# KoncovaCast_multi.net
KiCad netlist of a schematic drawn in EAGLE
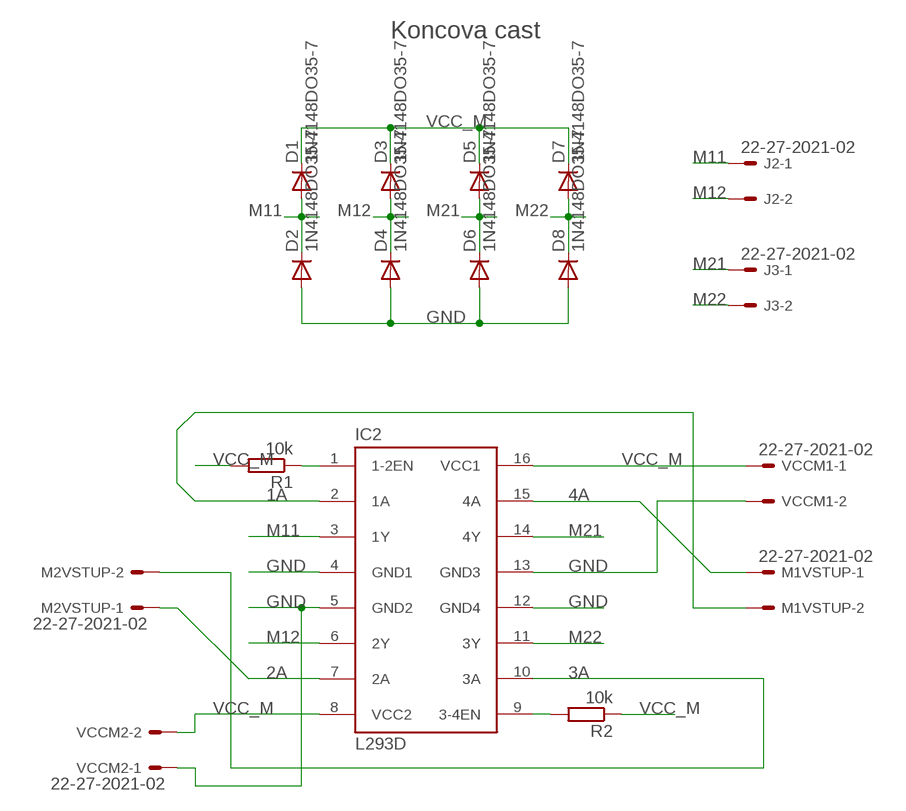
[diagram p0: schematic, sheet 1]

(export (version "E")
  (design (tool "Eeschema 10.0.6"))
  (components
    (comp (ref "D1")
      (value "1N4148DO35-7")
      (footprint "eagle-import:DO35-7")
      (libsource (lib "eagle-import") (part "1N4148DO35-7"))
    )
    (comp (ref "D2")
      (value "1N4148DO35-7")
      (footprint "eagle-import:DO35-7")
      (libsource (lib "eagle-import") (part "1N4148DO35-7"))
    )
    (comp (ref "D3")
      (value "1N4148DO35-7")
      (footprint "eagle-import:DO35-7")
      (libsource (lib "eagle-import") (part "1N4148DO35-7"))
    )
    (comp (ref "D4")
      (value "1N4148DO35-7")
      (footprint "eagle-import:DO35-7")
      (libsource (lib "eagle-import") (part "1N4148DO35-7"))
    )
    (comp (ref "D5")
      (value "1N4148DO35-7")
      (footprint "eagle-import:DO35-7")
      (libsource (lib "eagle-import") (part "1N4148DO35-7"))
    )
    (comp (ref "D6")
      (value "1N4148DO35-7")
      (footprint "eagle-import:DO35-7")
      (libsource (lib "eagle-import") (part "1N4148DO35-7"))
    )
    (comp (ref "D7")
      (value "1N4148DO35-7")
      (footprint "eagle-import:DO35-7")
      (libsource (lib "eagle-import") (part "1N4148DO35-7"))
    )
    (comp (ref "D8")
      (value "1N4148DO35-7")
      (footprint "eagle-import:DO35-7")
      (libsource (lib "eagle-import") (part "1N4148DO35-7"))
    )
    (comp (ref "IC2")
      (value "L293D")
      (footprint "eagle-import:DIL16")
      (libsource (lib "eagle-import") (part "L293D"))
    )
    (comp (ref "J2")
      (value "22-27-2021-02")
      (footprint "eagle-import:6410-02")
      (libsource (lib "eagle-import") (part "22-?-0227-2021"))
    )
    (comp (ref "J3")
      (value "22-27-2021-02")
      (footprint "eagle-import:6410-02")
      (libsource (lib "eagle-import") (part "22-?-0227-2021"))
    )
    (comp (ref "M1VSTUP")
      (value "22-27-2021-02")
      (footprint "eagle-import:6410-02")
      (libsource (lib "eagle-import") (part "22-?-0227-2021"))
    )
    (comp (ref "M2VSTUP")
      (value "22-27-2021-02")
      (footprint "eagle-import:6410-02")
      (libsource (lib "eagle-import") (part "22-?-0227-2021"))
    )
    (comp (ref "R1")
      (value "10k")
      (footprint "eagle-import:0204V")
      (libsource (lib "eagle-import") (part "R-EU_0204/2V"))
    )
    (comp (ref "R2")
      (value "10k")
      (footprint "eagle-import:0204V")
      (libsource (lib "eagle-import") (part "R-EU_0204/2V"))
    )
    (comp (ref "VCCM1")
      (value "22-27-2021-02")
      (footprint "eagle-import:6410-02")
      (libsource (lib "eagle-import") (part "22-?-0227-2021"))
    )
    (comp (ref "VCCM2")
      (value "22-27-2021-02")
      (footprint "eagle-import:6410-02")
      (libsource (lib "eagle-import") (part "22-?-0227-2021"))
    )
  )
  (nets
    (net (code "1") (name "/1A") (class "Default")
      (node (ref "IC2") (pin "2") (pinfunction "1A_2") (pintype "input"))
      (node (ref "M1VSTUP") (pin "2") (pinfunction "S_2") (pintype "passive"))
    )
    (net (code "2") (name "/2A") (class "Default")
      (node (ref "IC2") (pin "7") (pinfunction "2A_7") (pintype "input"))
      (node (ref "M2VSTUP") (pin "1") (pinfunction "S_1") (pintype "passive"))
    )
    (net (code "3") (name "/3A") (class "Default")
      (node (ref "IC2") (pin "10") (pinfunction "3A_10") (pintype "input"))
      (node (ref "M2VSTUP") (pin "2") (pinfunction "S_2") (pintype "passive"))
    )
    (net (code "4") (name "/4A") (class "Default")
      (node (ref "IC2") (pin "15") (pinfunction "4A_15") (pintype "input"))
      (node (ref "M1VSTUP") (pin "1") (pinfunction "S_1") (pintype "passive"))
    )
    (net (code "5") (name "/GND") (class "Default")
      (node (ref "D2") (pin "A") (pinfunction "A_A") (pintype "passive"))
      (node (ref "D4") (pin "A") (pinfunction "A_A") (pintype "passive"))
      (node (ref "D6") (pin "A") (pinfunction "A_A") (pintype "passive"))
      (node (ref "D8") (pin "A") (pinfunction "A_A") (pintype "passive"))
      (node (ref "IC2") (pin "12") (pinfunction "GND4_12") (pintype "power_in"))
      (node (ref "IC2") (pin "13") (pinfunction "GND3_13") (pintype "power_in"))
      (node (ref "IC2") (pin "4") (pinfunction "GND1_4") (pintype "power_in"))
      (node (ref "IC2") (pin "5") (pinfunction "GND2_5") (pintype "power_in"))
      (node (ref "VCCM1") (pin "2") (pinfunction "S_2") (pintype "passive"))
      (node (ref "VCCM2") (pin "1") (pinfunction "S_1") (pintype "passive"))
    )
    (net (code "6") (name "/M11") (class "Default")
      (node (ref "D1") (pin "A") (pinfunction "A_A") (pintype "passive"))
      (node (ref "D2") (pin "C") (pinfunction "C_C") (pintype "passive"))
      (node (ref "IC2") (pin "3") (pinfunction "1Y_3") (pintype "output"))
      (node (ref "J2") (pin "1") (pinfunction "S_1") (pintype "passive"))
    )
    (net (code "7") (name "/M12") (class "Default")
      (node (ref "D3") (pin "A") (pinfunction "A_A") (pintype "passive"))
      (node (ref "D4") (pin "C") (pinfunction "C_C") (pintype "passive"))
      (node (ref "IC2") (pin "6") (pinfunction "2Y_6") (pintype "output"))
      (node (ref "J2") (pin "2") (pinfunction "S_2") (pintype "passive"))
    )
    (net (code "8") (name "/M21") (class "Default")
      (node (ref "D5") (pin "A") (pinfunction "A_A") (pintype "passive"))
      (node (ref "D6") (pin "C") (pinfunction "C_C") (pintype "passive"))
      (node (ref "IC2") (pin "14") (pinfunction "4Y_14") (pintype "output"))
      (node (ref "J3") (pin "1") (pinfunction "S_1") (pintype "passive"))
    )
    (net (code "9") (name "/M22") (class "Default")
      (node (ref "D7") (pin "A") (pinfunction "A_A") (pintype "passive"))
      (node (ref "D8") (pin "C") (pinfunction "C_C") (pintype "passive"))
      (node (ref "IC2") (pin "11") (pinfunction "3Y_11") (pintype "output"))
      (node (ref "J3") (pin "2") (pinfunction "S_2") (pintype "passive"))
    )
    (net (code "10") (name "/VCC_M") (class "Default")
      (node (ref "D1") (pin "C") (pinfunction "C_C") (pintype "passive"))
      (node (ref "D3") (pin "C") (pinfunction "C_C") (pintype "passive"))
      (node (ref "D5") (pin "C") (pinfunction "C_C") (pintype "passive"))
      (node (ref "D7") (pin "C") (pinfunction "C_C") (pintype "passive"))
      (node (ref "IC2") (pin "16") (pinfunction "VCC1_16") (pintype "power_in"))
      (node (ref "IC2") (pin "8") (pinfunction "VCC2_8") (pintype "power_in"))
      (node (ref "R1") (pin "2") (pinfunction "2_2") (pintype "passive"))
      (node (ref "R2") (pin "1") (pinfunction "1_1") (pintype "passive"))
      (node (ref "VCCM1") (pin "1") (pinfunction "S_1") (pintype "passive"))
      (node (ref "VCCM2") (pin "2") (pinfunction "S_2") (pintype "passive"))
    )
    (net (code "11") (name "Net-(IC2-1-2EN)") (class "Default")
      (node (ref "IC2") (pin "1") (pinfunction "1-2EN_1") (pintype "input"))
      (node (ref "R1") (pin "1") (pinfunction "1_1") (pintype "passive"))
    )
    (net (code "12") (name "Net-(IC2-3-4EN)") (class "Default")
      (node (ref "IC2") (pin "9") (pinfunction "3-4EN_9") (pintype "input"))
      (node (ref "R2") (pin "2") (pinfunction "2_2") (pintype "passive"))
    )
  )
)
